# ADC_Mod_1.net
KiCad netlist of a schematic drawn in Altium Designer
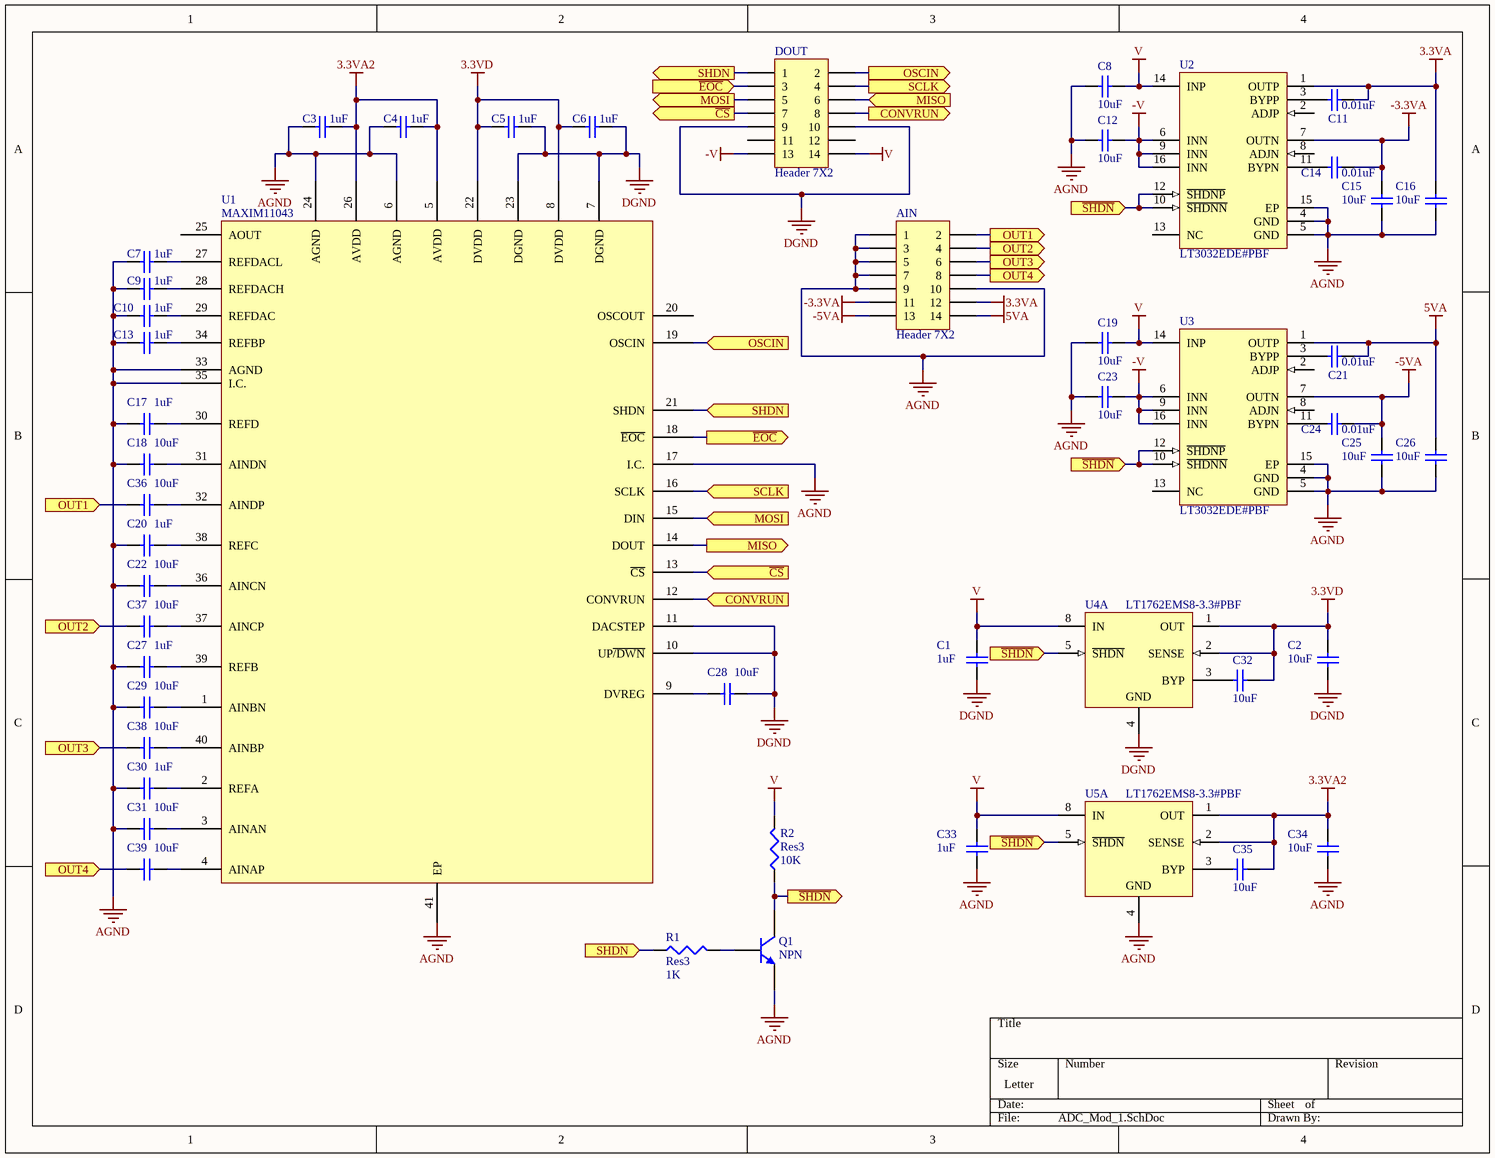
[diagram p0: ADC_Mod_1.SchDoc]

(export (version "E")
  (design (tool "Eeschema 10.0.6"))
  (components
    (comp (ref "AIN")
      (value "Header 7X2")
      (footprint "CONN_14x2_0.5IN")
      (description "Header, 7-Pin, Dual row")
      (fields (field (name "PUBLISHER") "Altium Limited"))
      (libsource (lib "Miscellaneous Connectors") (part "Header 7X2"))
    )
    (comp (ref "C1")
      (value "1uF")
      (footprint "0402")
      (description "Capacitor")
      (fields (field (name "Comment") "Cap") (field (name "PUBLISHER") "Altium Limited"))
      (libsource (lib "Miscellaneous Devices") (part "Cap"))
    )
    (comp (ref "C2")
      (value "10uF")
      (footprint "0402")
      (description "Capacitor")
      (fields (field (name "Comment") "Cap") (field (name "PUBLISHER") "Altium Limited"))
      (libsource (lib "Miscellaneous Devices") (part "Cap"))
    )
    (comp (ref "C3")
      (value "1uF")
      (footprint "0402")
      (description "Capacitor")
      (fields (field (name "Comment") "Cap") (field (name "PUBLISHER") "Altium Limited"))
      (libsource (lib "Miscellaneous Devices") (part "Cap"))
    )
    (comp (ref "C4")
      (value "1uF")
      (footprint "0402")
      (description "Capacitor")
      (fields (field (name "Comment") "Cap") (field (name "PUBLISHER") "Altium Limited"))
      (libsource (lib "Miscellaneous Devices") (part "Cap"))
    )
    (comp (ref "C5")
      (value "1uF")
      (footprint "0402")
      (description "Capacitor")
      (fields (field (name "Comment") "Cap") (field (name "PUBLISHER") "Altium Limited"))
      (libsource (lib "Miscellaneous Devices") (part "Cap"))
    )
    (comp (ref "C6")
      (value "1uF")
      (footprint "0402")
      (description "Capacitor")
      (fields (field (name "Comment") "Cap") (field (name "PUBLISHER") "Altium Limited"))
      (libsource (lib "Miscellaneous Devices") (part "Cap"))
    )
    (comp (ref "C7")
      (value "1uF")
      (footprint "0402")
      (description "Capacitor")
      (fields (field (name "Comment") "Cap") (field (name "PUBLISHER") "Altium Limited"))
      (libsource (lib "Miscellaneous Devices") (part "Cap"))
    )
    (comp (ref "C8")
      (value "10uF")
      (footprint "0402")
      (description "Capacitor")
      (fields (field (name "Comment") "Cap") (field (name "PUBLISHER") "Altium Limited"))
      (libsource (lib "Miscellaneous Devices") (part "Cap"))
    )
    (comp (ref "C9")
      (value "1uF")
      (footprint "0402")
      (description "Capacitor")
      (fields (field (name "Comment") "Cap") (field (name "PUBLISHER") "Altium Limited"))
      (libsource (lib "Miscellaneous Devices") (part "Cap"))
    )
    (comp (ref "C10")
      (value "1uF")
      (footprint "0402")
      (description "Capacitor")
      (fields (field (name "Comment") "Cap") (field (name "PUBLISHER") "Altium Limited"))
      (libsource (lib "Miscellaneous Devices") (part "Cap"))
    )
    (comp (ref "C11")
      (value "0.01uF")
      (footprint "0402")
      (description "Capacitor")
      (fields (field (name "Comment") "Cap") (field (name "PUBLISHER") "Altium Limited"))
      (libsource (lib "Miscellaneous Devices") (part "Cap"))
    )
    (comp (ref "C12")
      (value "10uF")
      (footprint "0402")
      (description "Capacitor")
      (fields (field (name "Comment") "Cap") (field (name "PUBLISHER") "Altium Limited"))
      (libsource (lib "Miscellaneous Devices") (part "Cap"))
    )
    (comp (ref "C13")
      (value "1uF")
      (footprint "0402")
      (description "Capacitor")
      (fields (field (name "Comment") "Cap") (field (name "PUBLISHER") "Altium Limited"))
      (libsource (lib "Miscellaneous Devices") (part "Cap"))
    )
    (comp (ref "C14")
      (value "0.01uF")
      (footprint "0402")
      (description "Capacitor")
      (fields (field (name "Comment") "Cap") (field (name "PUBLISHER") "Altium Limited"))
      (libsource (lib "Miscellaneous Devices") (part "Cap"))
    )
    (comp (ref "C15")
      (value "10uF")
      (footprint "0402")
      (description "Capacitor")
      (fields (field (name "Comment") "Cap") (field (name "PUBLISHER") "Altium Limited"))
      (libsource (lib "Miscellaneous Devices") (part "Cap"))
    )
    (comp (ref "C16")
      (value "10uF")
      (footprint "0402")
      (description "Capacitor")
      (fields (field (name "Comment") "Cap") (field (name "PUBLISHER") "Altium Limited"))
      (libsource (lib "Miscellaneous Devices") (part "Cap"))
    )
    (comp (ref "C17")
      (value "1uF")
      (footprint "0402")
      (description "Capacitor")
      (fields (field (name "Comment") "Cap") (field (name "PUBLISHER") "Altium Limited"))
      (libsource (lib "Miscellaneous Devices") (part "Cap"))
    )
    (comp (ref "C18")
      (value "10uF")
      (footprint "0402")
      (description "Capacitor")
      (fields (field (name "Comment") "Cap") (field (name "PUBLISHER") "Altium Limited"))
      (libsource (lib "Miscellaneous Devices") (part "Cap"))
    )
    (comp (ref "C19")
      (value "10uF")
      (footprint "0402")
      (description "Capacitor")
      (fields (field (name "Comment") "Cap") (field (name "PUBLISHER") "Altium Limited"))
      (libsource (lib "Miscellaneous Devices") (part "Cap"))
    )
    (comp (ref "C20")
      (value "1uF")
      (footprint "0402")
      (description "Capacitor")
      (fields (field (name "Comment") "Cap") (field (name "PUBLISHER") "Altium Limited"))
      (libsource (lib "Miscellaneous Devices") (part "Cap"))
    )
    (comp (ref "C21")
      (value "0.01uF")
      (footprint "0402")
      (description "Capacitor")
      (fields (field (name "Comment") "Cap") (field (name "PUBLISHER") "Altium Limited"))
      (libsource (lib "Miscellaneous Devices") (part "Cap"))
    )
    (comp (ref "C22")
      (value "10uF")
      (footprint "0402")
      (description "Capacitor")
      (fields (field (name "Comment") "Cap") (field (name "PUBLISHER") "Altium Limited"))
      (libsource (lib "Miscellaneous Devices") (part "Cap"))
    )
    (comp (ref "C23")
      (value "10uF")
      (footprint "0402")
      (description "Capacitor")
      (fields (field (name "Comment") "Cap") (field (name "PUBLISHER") "Altium Limited"))
      (libsource (lib "Miscellaneous Devices") (part "Cap"))
    )
    (comp (ref "C24")
      (value "0.01uF")
      (footprint "0402")
      (description "Capacitor")
      (fields (field (name "Comment") "Cap") (field (name "PUBLISHER") "Altium Limited"))
      (libsource (lib "Miscellaneous Devices") (part "Cap"))
    )
    (comp (ref "C25")
      (value "10uF")
      (footprint "0402")
      (description "Capacitor")
      (fields (field (name "Comment") "Cap") (field (name "PUBLISHER") "Altium Limited"))
      (libsource (lib "Miscellaneous Devices") (part "Cap"))
    )
    (comp (ref "C26")
      (value "10uF")
      (footprint "0402")
      (description "Capacitor")
      (fields (field (name "Comment") "Cap") (field (name "PUBLISHER") "Altium Limited"))
      (libsource (lib "Miscellaneous Devices") (part "Cap"))
    )
    (comp (ref "C27")
      (value "1uF")
      (footprint "0402")
      (description "Capacitor")
      (fields (field (name "Comment") "Cap") (field (name "PUBLISHER") "Altium Limited"))
      (libsource (lib "Miscellaneous Devices") (part "Cap"))
    )
    (comp (ref "C28")
      (value "10uF")
      (footprint "0402")
      (description "Capacitor")
      (fields (field (name "Comment") "Cap") (field (name "PUBLISHER") "Altium Limited"))
      (libsource (lib "Miscellaneous Devices") (part "Cap"))
    )
    (comp (ref "C29")
      (value "10uF")
      (footprint "0402")
      (description "Capacitor")
      (fields (field (name "Comment") "Cap") (field (name "PUBLISHER") "Altium Limited"))
      (libsource (lib "Miscellaneous Devices") (part "Cap"))
    )
    (comp (ref "C30")
      (value "1uF")
      (footprint "0402")
      (description "Capacitor")
      (fields (field (name "Comment") "Cap") (field (name "PUBLISHER") "Altium Limited"))
      (libsource (lib "Miscellaneous Devices") (part "Cap"))
    )
    (comp (ref "C31")
      (value "10uF")
      (footprint "0402")
      (description "Capacitor")
      (fields (field (name "Comment") "Cap") (field (name "PUBLISHER") "Altium Limited"))
      (libsource (lib "Miscellaneous Devices") (part "Cap"))
    )
    (comp (ref "C32")
      (value "10uF")
      (footprint "0402")
      (description "Capacitor")
      (fields (field (name "Comment") "Cap") (field (name "PUBLISHER") "Altium Limited"))
      (libsource (lib "Miscellaneous Devices") (part "Cap"))
    )
    (comp (ref "C33")
      (value "1uF")
      (footprint "0402")
      (description "Capacitor")
      (fields (field (name "Comment") "Cap") (field (name "PUBLISHER") "Altium Limited"))
      (libsource (lib "Miscellaneous Devices") (part "Cap"))
    )
    (comp (ref "C34")
      (value "10uF")
      (footprint "0402")
      (description "Capacitor")
      (fields (field (name "Comment") "Cap") (field (name "PUBLISHER") "Altium Limited"))
      (libsource (lib "Miscellaneous Devices") (part "Cap"))
    )
    (comp (ref "C35")
      (value "10uF")
      (footprint "0402")
      (description "Capacitor")
      (fields (field (name "Comment") "Cap") (field (name "PUBLISHER") "Altium Limited"))
      (libsource (lib "Miscellaneous Devices") (part "Cap"))
    )
    (comp (ref "C36")
      (value "10uF")
      (footprint "0402")
      (description "Capacitor")
      (fields (field (name "Comment") "Cap") (field (name "PUBLISHER") "Altium Limited"))
      (libsource (lib "Miscellaneous Devices") (part "Cap"))
    )
    (comp (ref "C37")
      (value "10uF")
      (footprint "0402")
      (description "Capacitor")
      (fields (field (name "Comment") "Cap") (field (name "PUBLISHER") "Altium Limited"))
      (libsource (lib "Miscellaneous Devices") (part "Cap"))
    )
    (comp (ref "C38")
      (value "10uF")
      (footprint "0402")
      (description "Capacitor")
      (fields (field (name "Comment") "Cap") (field (name "PUBLISHER") "Altium Limited"))
      (libsource (lib "Miscellaneous Devices") (part "Cap"))
    )
    (comp (ref "C39")
      (value "10uF")
      (footprint "0402")
      (description "Capacitor")
      (fields (field (name "Comment") "Cap") (field (name "PUBLISHER") "Altium Limited"))
      (libsource (lib "Miscellaneous Devices") (part "Cap"))
    )
    (comp (ref "DOUT")
      (value "Header 7X2")
      (footprint "CONN_14x2_0.5IN")
      (description "Header, 7-Pin, Dual row")
      (fields (field (name "PUBLISHER") "Altium Limited"))
      (libsource (lib "Miscellaneous Connectors") (part "Header 7X2"))
    )
    (comp (ref "Q1")
      (value "NPN")
      (footprint "SOT23_L")
      (description "NPN Bipolar Transistor")
      (fields (field (name "PUBLISHER") "Altium Limited"))
      (libsource (lib "Miscellaneous Devices") (part "NPN"))
    )
    (comp (ref "R1")
      (value "Res3")
      (footprint "J1-0603")
      (description "Resistor")
      (fields (field (name "ALTIUM_VALUE") "1K") (field (name "PUBLISHER") "Altium Limited"))
      (libsource (lib "Miscellaneous Devices") (part "Res3"))
    )
    (comp (ref "R2")
      (value "Res3")
      (footprint "J1-0603")
      (description "Resistor")
      (fields (field (name "ALTIUM_VALUE") "10K") (field (name "PUBLISHER") "Altium Limited"))
      (libsource (lib "Miscellaneous Devices") (part "Res3"))
    )
    (comp (ref "U1")
      (value "MAXIM11043")
      (footprint "21-0141I_T406600")
      (libsource (lib "MAXIM11043") (part "MAXIM11043"))
    )
    (comp (ref "U2")
      (value "LT3032EDE#PBF")
      (footprint "LT-DE14MA-14_V")
      (fields (field (name "MANUFACTURER") "Linear Technology"))
      (libsource (lib "Linear Technology Power Management LDO Linear Regulators") (part "LT3032EDE#PBF"))
    )
    (comp (ref "U3")
      (value "LT3032EDE#PBF")
      (footprint "LT-DE14MA-14_V")
      (fields (field (name "MANUFACTURER") "Linear Technology"))
      (libsource (lib "Linear Technology Power Management LDO Linear Regulators") (part "LT3032EDE#PBF"))
    )
    (comp (ref "U4")
      (value "LT1762EMS8-3.3#PBF")
      (footprint "LT-MS8_N")
      (fields (field (name "MANUFACTURER") "Linear Technology"))
      (libsource (lib "Linear Technology Power Management LDO Linear Regulators") (part "LT1762EMS8-3.3#PBF"))
    )
    (comp (ref "U5")
      (value "LT1762EMS8-3.3#PBF")
      (footprint "LT-MS8_N")
      (fields (field (name "MANUFACTURER") "Linear Technology"))
      (libsource (lib "Linear Technology Power Management LDO Linear Regulators") (part "LT1762EMS8-3.3#PBF"))
    )
  )
  (nets
    (net (code "1") (name "-3.3VA") (class "Default")
      (node (ref "AIN") (pin "11") (pinfunction "11_11") (pintype "passive"))
      (node (ref "C14") (pin "2") (pinfunction "2_2") (pintype "passive"))
      (node (ref "C15") (pin "2") (pinfunction "2_2") (pintype "passive"))
      (node (ref "U2") (pin "7") (pinfunction "OUTN_7") (pintype "power_in"))
    )
    (net (code "2") (name "-5VA") (class "Default")
      (node (ref "AIN") (pin "13") (pinfunction "13_13") (pintype "passive"))
      (node (ref "C24") (pin "2") (pinfunction "2_2") (pintype "passive"))
      (node (ref "C25") (pin "2") (pinfunction "2_2") (pintype "passive"))
      (node (ref "U3") (pin "7") (pinfunction "OUTN_7") (pintype "power_in"))
    )
    (net (code "3") (name "-V") (class "Default")
      (node (ref "C12") (pin "1") (pinfunction "1_1") (pintype "passive"))
      (node (ref "C23") (pin "1") (pinfunction "1_1") (pintype "passive"))
      (node (ref "DOUT") (pin "13") (pinfunction "13_13") (pintype "passive"))
      (node (ref "U2") (pin "16") (pinfunction "INN_16") (pintype "power_in"))
      (node (ref "U2") (pin "6") (pinfunction "INN_6") (pintype "power_in"))
      (node (ref "U2") (pin "9") (pinfunction "INN_9") (pintype "power_in"))
      (node (ref "U3") (pin "16") (pinfunction "INN_16") (pintype "power_in"))
      (node (ref "U3") (pin "6") (pinfunction "INN_6") (pintype "power_in"))
      (node (ref "U3") (pin "9") (pinfunction "INN_9") (pintype "power_in"))
    )
    (net (code "4") (name "/CONVRUN") (class "Default")
      (node (ref "DOUT") (pin "8") (pinfunction "8_8") (pintype "passive"))
      (node (ref "U1") (pin "12") (pinfunction "CONVRUN_12") (pintype "passive"))
    )
    (net (code "5") (name "/MISO") (class "Default")
      (node (ref "DOUT") (pin "6") (pinfunction "6_6") (pintype "passive"))
      (node (ref "U1") (pin "14") (pinfunction "DOUT_14") (pintype "passive"))
    )
    (net (code "6") (name "/MOSI") (class "Default")
      (node (ref "DOUT") (pin "5") (pinfunction "5_5") (pintype "passive"))
      (node (ref "U1") (pin "15") (pinfunction "DIN_15") (pintype "passive"))
    )
    (net (code "7") (name "/OSCIN") (class "Default")
      (node (ref "DOUT") (pin "2") (pinfunction "2_2") (pintype "passive"))
      (node (ref "U1") (pin "19") (pinfunction "OSCIN_19") (pintype "passive"))
    )
    (net (code "8") (name "/OUT1") (class "Default")
      (node (ref "AIN") (pin "2") (pinfunction "2_2") (pintype "passive"))
      (node (ref "C36") (pin "1") (pinfunction "1_1") (pintype "passive"))
    )
    (net (code "9") (name "/OUT2") (class "Default")
      (node (ref "AIN") (pin "4") (pinfunction "4_4") (pintype "passive"))
      (node (ref "C37") (pin "1") (pinfunction "1_1") (pintype "passive"))
    )
    (net (code "10") (name "/OUT3") (class "Default")
      (node (ref "AIN") (pin "6") (pinfunction "6_6") (pintype "passive"))
      (node (ref "C38") (pin "1") (pinfunction "1_1") (pintype "passive"))
    )
    (net (code "11") (name "/OUT4") (class "Default")
      (node (ref "AIN") (pin "8") (pinfunction "8_8") (pintype "passive"))
      (node (ref "C39") (pin "1") (pinfunction "1_1") (pintype "passive"))
    )
    (net (code "12") (name "/SCLK") (class "Default")
      (node (ref "DOUT") (pin "4") (pinfunction "4_4") (pintype "passive"))
      (node (ref "U1") (pin "16") (pinfunction "SCLK_16") (pintype "passive"))
    )
    (net (code "13") (name "/SHDN") (class "Default")
      (node (ref "DOUT") (pin "1") (pinfunction "1_1") (pintype "passive"))
      (node (ref "R1") (pin "1") (pinfunction "1_1") (pintype "passive"))
      (node (ref "U1") (pin "21") (pinfunction "SHDN_21") (pintype "passive"))
    )
    (net (code "14") (name "/~{CS}") (class "Default")
      (node (ref "DOUT") (pin "7") (pinfunction "7_7") (pintype "passive"))
      (node (ref "U1") (pin "13") (pinfunction "~{CS}_13") (pintype "passive"))
    )
    (net (code "15") (name "/~{EOC}") (class "Default")
      (node (ref "DOUT") (pin "3") (pinfunction "3_3") (pintype "passive"))
      (node (ref "U1") (pin "18") (pinfunction "~{EOC}_18") (pintype "passive"))
    )
    (net (code "16") (name "/~{SHDN}") (class "Default")
      (node (ref "Q1") (pin "1") (pinfunction "C_1") (pintype "passive"))
      (node (ref "R2") (pin "1") (pinfunction "1_1") (pintype "passive"))
      (node (ref "U2") (pin "10") (pinfunction "~{SHDNN}_10") (pintype "input"))
      (node (ref "U2") (pin "12") (pinfunction "~{SHDNP}_12") (pintype "input"))
      (node (ref "U3") (pin "10") (pinfunction "~{SHDNN}_10") (pintype "input"))
      (node (ref "U3") (pin "12") (pinfunction "~{SHDNP}_12") (pintype "input"))
      (node (ref "U4") (pin "5") (pinfunction "~{SHDN}_5") (pintype "input"))
      (node (ref "U5") (pin "5") (pinfunction "~{SHDN}_5") (pintype "input"))
    )
    (net (code "17") (name "3.3VA") (class "Default")
      (node (ref "AIN") (pin "12") (pinfunction "12_12") (pintype "passive"))
      (node (ref "C11") (pin "2") (pinfunction "2_2") (pintype "passive"))
      (node (ref "C16") (pin "2") (pinfunction "2_2") (pintype "passive"))
      (node (ref "U2") (pin "1") (pinfunction "OUTP_1") (pintype "power_in"))
    )
    (net (code "18") (name "3.3VA2") (class "Default")
      (node (ref "C3") (pin "2") (pinfunction "2_2") (pintype "passive"))
      (node (ref "C34") (pin "2") (pinfunction "2_2") (pintype "passive"))
      (node (ref "C35") (pin "1") (pinfunction "1_1") (pintype "passive"))
      (node (ref "C4") (pin "2") (pinfunction "2_2") (pintype "passive"))
      (node (ref "U1") (pin "26") (pinfunction "AVDD_26") (pintype "passive"))
      (node (ref "U1") (pin "5") (pinfunction "AVDD_5") (pintype "passive"))
      (node (ref "U5") (pin "1") (pinfunction "OUT_1") (pintype "power_in"))
      (node (ref "U5") (pin "2") (pinfunction "SENSE_2") (pintype "input"))
    )
    (net (code "19") (name "3.3VD") (class "Default")
      (node (ref "C2") (pin "2") (pinfunction "2_2") (pintype "passive"))
      (node (ref "C32") (pin "1") (pinfunction "1_1") (pintype "passive"))
      (node (ref "C5") (pin "1") (pinfunction "1_1") (pintype "passive"))
      (node (ref "C6") (pin "1") (pinfunction "1_1") (pintype "passive"))
      (node (ref "U1") (pin "22") (pinfunction "DVDD_22") (pintype "passive"))
      (node (ref "U1") (pin "8") (pinfunction "DVDD_8") (pintype "passive"))
      (node (ref "U4") (pin "1") (pinfunction "OUT_1") (pintype "power_in"))
      (node (ref "U4") (pin "2") (pinfunction "SENSE_2") (pintype "input"))
    )
    (net (code "20") (name "5VA") (class "Default")
      (node (ref "AIN") (pin "14") (pinfunction "14_14") (pintype "passive"))
      (node (ref "C21") (pin "2") (pinfunction "2_2") (pintype "passive"))
      (node (ref "C26") (pin "2") (pinfunction "2_2") (pintype "passive"))
      (node (ref "U3") (pin "1") (pinfunction "OUTP_1") (pintype "power_in"))
    )
    (net (code "21") (name "AGND") (class "Default")
      (node (ref "AIN") (pin "1") (pinfunction "1_1") (pintype "passive"))
      (node (ref "AIN") (pin "10") (pinfunction "10_10") (pintype "passive"))
      (node (ref "AIN") (pin "3") (pinfunction "3_3") (pintype "passive"))
      (node (ref "AIN") (pin "5") (pinfunction "5_5") (pintype "passive"))
      (node (ref "AIN") (pin "7") (pinfunction "7_7") (pintype "passive"))
      (node (ref "AIN") (pin "9") (pinfunction "9_9") (pintype "passive"))
      (node (ref "C10") (pin "1") (pinfunction "1_1") (pintype "passive"))
      (node (ref "C12") (pin "2") (pinfunction "2_2") (pintype "passive"))
      (node (ref "C13") (pin "1") (pinfunction "1_1") (pintype "passive"))
      (node (ref "C15") (pin "1") (pinfunction "1_1") (pintype "passive"))
      (node (ref "C16") (pin "1") (pinfunction "1_1") (pintype "passive"))
      (node (ref "C17") (pin "1") (pinfunction "1_1") (pintype "passive"))
      (node (ref "C18") (pin "1") (pinfunction "1_1") (pintype "passive"))
      (node (ref "C19") (pin "2") (pinfunction "2_2") (pintype "passive"))
      (node (ref "C20") (pin "1") (pinfunction "1_1") (pintype "passive"))
      (node (ref "C22") (pin "1") (pinfunction "1_1") (pintype "passive"))
      (node (ref "C23") (pin "2") (pinfunction "2_2") (pintype "passive"))
      (node (ref "C25") (pin "1") (pinfunction "1_1") (pintype "passive"))
      (node (ref "C26") (pin "1") (pinfunction "1_1") (pintype "passive"))
      (node (ref "C27") (pin "1") (pinfunction "1_1") (pintype "passive"))
      (node (ref "C29") (pin "1") (pinfunction "1_1") (pintype "passive"))
      (node (ref "C3") (pin "1") (pinfunction "1_1") (pintype "passive"))
      (node (ref "C30") (pin "1") (pinfunction "1_1") (pintype "passive"))
      (node (ref "C31") (pin "1") (pinfunction "1_1") (pintype "passive"))
      (node (ref "C33") (pin "1") (pinfunction "1_1") (pintype "passive"))
      (node (ref "C34") (pin "1") (pinfunction "1_1") (pintype "passive"))
      (node (ref "C4") (pin "1") (pinfunction "1_1") (pintype "passive"))
      (node (ref "C7") (pin "1") (pinfunction "1_1") (pintype "passive"))
      (node (ref "C8") (pin "2") (pinfunction "2_2") (pintype "passive"))
      (node (ref "C9") (pin "1") (pinfunction "1_1") (pintype "passive"))
      (node (ref "Q1") (pin "3") (pinfunction "E_3") (pintype "passive"))
      (node (ref "U1") (pin "17") (pinfunction "I.C._17") (pintype "passive"))
      (node (ref "U1") (pin "24") (pinfunction "AGND_24") (pintype "passive"))
      (node (ref "U1") (pin "33") (pinfunction "AGND_33") (pintype "passive"))
      (node (ref "U1") (pin "35") (pinfunction "I.C._35") (pintype "passive"))
      (node (ref "U1") (pin "41") (pinfunction "EP_41") (pintype "passive"))
      (node (ref "U1") (pin "6") (pinfunction "AGND_6") (pintype "passive"))
      (node (ref "U2") (pin "15") (pinfunction "EP_15") (pintype "power_in"))
      (node (ref "U2") (pin "4") (pinfunction "GND_4") (pintype "power_in"))
      (node (ref "U2") (pin "5") (pinfunction "GND_5") (pintype "power_in"))
      (node (ref "U3") (pin "15") (pinfunction "EP_15") (pintype "power_in"))
      (node (ref "U3") (pin "4") (pinfunction "GND_4") (pintype "power_in"))
      (node (ref "U3") (pin "5") (pinfunction "GND_5") (pintype "power_in"))
      (node (ref "U5") (pin "4") (pinfunction "GND_4") (pintype "power_in"))
    )
    (net (code "22") (name "DGND") (class "Default")
      (node (ref "C1") (pin "1") (pinfunction "1_1") (pintype "passive"))
      (node (ref "C2") (pin "1") (pinfunction "1_1") (pintype "passive"))
      (node (ref "C28") (pin "2") (pinfunction "2_2") (pintype "passive"))
      (node (ref "C5") (pin "2") (pinfunction "2_2") (pintype "passive"))
      (node (ref "C6") (pin "2") (pinfunction "2_2") (pintype "passive"))
      (node (ref "DOUT") (pin "10") (pinfunction "10_10") (pintype "passive"))
      (node (ref "DOUT") (pin "9") (pinfunction "9_9") (pintype "passive"))
      (node (ref "U1") (pin "10") (pinfunction "UP~{/DWN}_10") (pintype "passive"))
      (node (ref "U1") (pin "11") (pinfunction "DACSTEP_11") (pintype "passive"))
      (node (ref "U1") (pin "23") (pinfunction "DGND_23") (pintype "passive"))
      (node (ref "U1") (pin "7") (pinfunction "DGND_7") (pintype "passive"))
      (node (ref "U4") (pin "4") (pinfunction "GND_4") (pintype "power_in"))
    )
    (net (code "23") (name "Net-(Q1-B)") (class "Default")
      (node (ref "Q1") (pin "2") (pinfunction "B_2") (pintype "passive"))
      (node (ref "R1") (pin "2") (pinfunction "2_2") (pintype "passive"))
    )
    (net (code "24") (name "Net-(U1-AINAN)") (class "Default")
      (node (ref "C31") (pin "2") (pinfunction "2_2") (pintype "passive"))
      (node (ref "U1") (pin "3") (pinfunction "AINAN_3") (pintype "passive"))
    )
    (net (code "25") (name "Net-(U1-AINAP)") (class "Default")
      (node (ref "C39") (pin "2") (pinfunction "2_2") (pintype "passive"))
      (node (ref "U1") (pin "4") (pinfunction "AINAP_4") (pintype "passive"))
    )
    (net (code "26") (name "Net-(U1-AINBN)") (class "Default")
      (node (ref "C29") (pin "2") (pinfunction "2_2") (pintype "passive"))
      (node (ref "U1") (pin "1") (pinfunction "AINBN_1") (pintype "passive"))
    )
    (net (code "27") (name "Net-(U1-AINBP)") (class "Default")
      (node (ref "C38") (pin "2") (pinfunction "2_2") (pintype "passive"))
      (node (ref "U1") (pin "40") (pinfunction "AINBP_40") (pintype "passive"))
    )
    (net (code "28") (name "Net-(U1-AINCN)") (class "Default")
      (node (ref "C22") (pin "2") (pinfunction "2_2") (pintype "passive"))
      (node (ref "U1") (pin "36") (pinfunction "AINCN_36") (pintype "passive"))
    )
    (net (code "29") (name "Net-(U1-AINCP)") (class "Default")
      (node (ref "C37") (pin "2") (pinfunction "2_2") (pintype "passive"))
      (node (ref "U1") (pin "37") (pinfunction "AINCP_37") (pintype "passive"))
    )
    (net (code "30") (name "Net-(U1-AINDN)") (class "Default")
      (node (ref "C18") (pin "2") (pinfunction "2_2") (pintype "passive"))
      (node (ref "U1") (pin "31") (pinfunction "AINDN_31") (pintype "passive"))
    )
    (net (code "31") (name "Net-(U1-AINDP)") (class "Default")
      (node (ref "C36") (pin "2") (pinfunction "2_2") (pintype "passive"))
      (node (ref "U1") (pin "32") (pinfunction "AINDP_32") (pintype "passive"))
    )
    (net (code "32") (name "Net-(U1-DVREG)") (class "Default")
      (node (ref "C28") (pin "1") (pinfunction "1_1") (pintype "passive"))
      (node (ref "U1") (pin "9") (pinfunction "DVREG_9") (pintype "passive"))
    )
    (net (code "33") (name "Net-(U1-REFA)") (class "Default")
      (node (ref "C30") (pin "2") (pinfunction "2_2") (pintype "passive"))
      (node (ref "U1") (pin "2") (pinfunction "REFA_2") (pintype "passive"))
    )
    (net (code "34") (name "Net-(U1-REFB)") (class "Default")
      (node (ref "C27") (pin "2") (pinfunction "2_2") (pintype "passive"))
      (node (ref "U1") (pin "39") (pinfunction "REFB_39") (pintype "passive"))
    )
    (net (code "35") (name "Net-(U1-REFBP)") (class "Default")
      (node (ref "C13") (pin "2") (pinfunction "2_2") (pintype "passive"))
      (node (ref "U1") (pin "34") (pinfunction "REFBP_34") (pintype "passive"))
    )
    (net (code "36") (name "Net-(U1-REFC)") (class "Default")
      (node (ref "C20") (pin "2") (pinfunction "2_2") (pintype "passive"))
      (node (ref "U1") (pin "38") (pinfunction "REFC_38") (pintype "passive"))
    )
    (net (code "37") (name "Net-(U1-REFD)") (class "Default")
      (node (ref "C17") (pin "2") (pinfunction "2_2") (pintype "passive"))
      (node (ref "U1") (pin "30") (pinfunction "REFD_30") (pintype "passive"))
    )
    (net (code "38") (name "Net-(U1-REFDAC)") (class "Default")
      (node (ref "C10") (pin "2") (pinfunction "2_2") (pintype "passive"))
      (node (ref "U1") (pin "29") (pinfunction "REFDAC_29") (pintype "passive"))
    )
    (net (code "39") (name "Net-(U1-REFDACH)") (class "Default")
      (node (ref "C9") (pin "2") (pinfunction "2_2") (pintype "passive"))
      (node (ref "U1") (pin "28") (pinfunction "REFDACH_28") (pintype "passive"))
    )
    (net (code "40") (name "Net-(U1-REFDACL)") (class "Default")
      (node (ref "C7") (pin "2") (pinfunction "2_2") (pintype "passive"))
      (node (ref "U1") (pin "27") (pinfunction "REFDACL_27") (pintype "passive"))
    )
    (net (code "41") (name "Net-(U2-BYPN)") (class "Default")
      (node (ref "C14") (pin "1") (pinfunction "1_1") (pintype "passive"))
      (node (ref "U2") (pin "11") (pinfunction "BYPN_11") (pintype "passive"))
    )
    (net (code "42") (name "Net-(U2-BYPP)") (class "Default")
      (node (ref "C11") (pin "1") (pinfunction "1_1") (pintype "passive"))
      (node (ref "U2") (pin "3") (pinfunction "BYPP_3") (pintype "passive"))
    )
    (net (code "43") (name "Net-(U3-BYPN)") (class "Default")
      (node (ref "C24") (pin "1") (pinfunction "1_1") (pintype "passive"))
      (node (ref "U3") (pin "11") (pinfunction "BYPN_11") (pintype "passive"))
    )
    (net (code "44") (name "Net-(U3-BYPP)") (class "Default")
      (node (ref "C21") (pin "1") (pinfunction "1_1") (pintype "passive"))
      (node (ref "U3") (pin "3") (pinfunction "BYPP_3") (pintype "passive"))
    )
    (net (code "45") (name "Net-(U4A-BYP)") (class "Default")
      (node (ref "C32") (pin "2") (pinfunction "2_2") (pintype "passive"))
      (node (ref "U4") (pin "3") (pinfunction "BYP_3") (pintype "passive"))
    )
    (net (code "46") (name "Net-(U5A-BYP)") (class "Default")
      (node (ref "C35") (pin "2") (pinfunction "2_2") (pintype "passive"))
      (node (ref "U5") (pin "3") (pinfunction "BYP_3") (pintype "passive"))
    )
    (net (code "47") (name "V") (class "Default")
      (node (ref "C1") (pin "2") (pinfunction "2_2") (pintype "passive"))
      (node (ref "C19") (pin "1") (pinfunction "1_1") (pintype "passive"))
      (node (ref "C33") (pin "2") (pinfunction "2_2") (pintype "passive"))
      (node (ref "C8") (pin "1") (pinfunction "1_1") (pintype "passive"))
      (node (ref "DOUT") (pin "14") (pinfunction "14_14") (pintype "passive"))
      (node (ref "R2") (pin "2") (pinfunction "2_2") (pintype "passive"))
      (node (ref "U2") (pin "14") (pinfunction "INP_14") (pintype "power_in"))
      (node (ref "U3") (pin "14") (pinfunction "INP_14") (pintype "power_in"))
      (node (ref "U4") (pin "8") (pinfunction "IN_8") (pintype "power_in"))
      (node (ref "U5") (pin "8") (pinfunction "IN_8") (pintype "power_in"))
    )
    (net (code "48") (name "unconnected-(DOUT-Pad11)") (class "Default")
      (node (ref "DOUT") (pin "11") (pinfunction "11_11") (pintype "passive"))
    )
    (net (code "49") (name "unconnected-(DOUT-Pad12)") (class "Default")
      (node (ref "DOUT") (pin "12") (pinfunction "12_12") (pintype "passive"))
    )
    (net (code "50") (name "unconnected-(U1-AOUT-Pad25)") (class "Default")
      (node (ref "U1") (pin "25") (pinfunction "AOUT_25") (pintype "passive"))
    )
    (net (code "51") (name "unconnected-(U1-OSCOUT-Pad20)") (class "Default")
      (node (ref "U1") (pin "20") (pinfunction "OSCOUT_20") (pintype "passive"))
    )
    (net (code "52") (name "unconnected-(U2-ADJN-Pad8)") (class "Default")
      (node (ref "U2") (pin "8") (pinfunction "ADJN_8") (pintype "input"))
    )
    (net (code "53") (name "unconnected-(U2-ADJP-Pad2)") (class "Default")
      (node (ref "U2") (pin "2") (pinfunction "ADJP_2") (pintype "input"))
    )
    (net (code "54") (name "unconnected-(U2-NC-Pad13)") (class "Default")
      (node (ref "U2") (pin "13") (pinfunction "NC_13") (pintype "passive"))
    )
    (net (code "55") (name "unconnected-(U3-ADJN-Pad8)") (class "Default")
      (node (ref "U3") (pin "8") (pinfunction "ADJN_8") (pintype "input"))
    )
    (net (code "56") (name "unconnected-(U3-ADJP-Pad2)") (class "Default")
      (node (ref "U3") (pin "2") (pinfunction "ADJP_2") (pintype "input"))
    )
    (net (code "57") (name "unconnected-(U3-NC-Pad13)") (class "Default")
      (node (ref "U3") (pin "13") (pinfunction "NC_13") (pintype "passive"))
    )
  )
)
